# sensor_v2.net
KiCad netlist of a schematic drawn in EAGLE
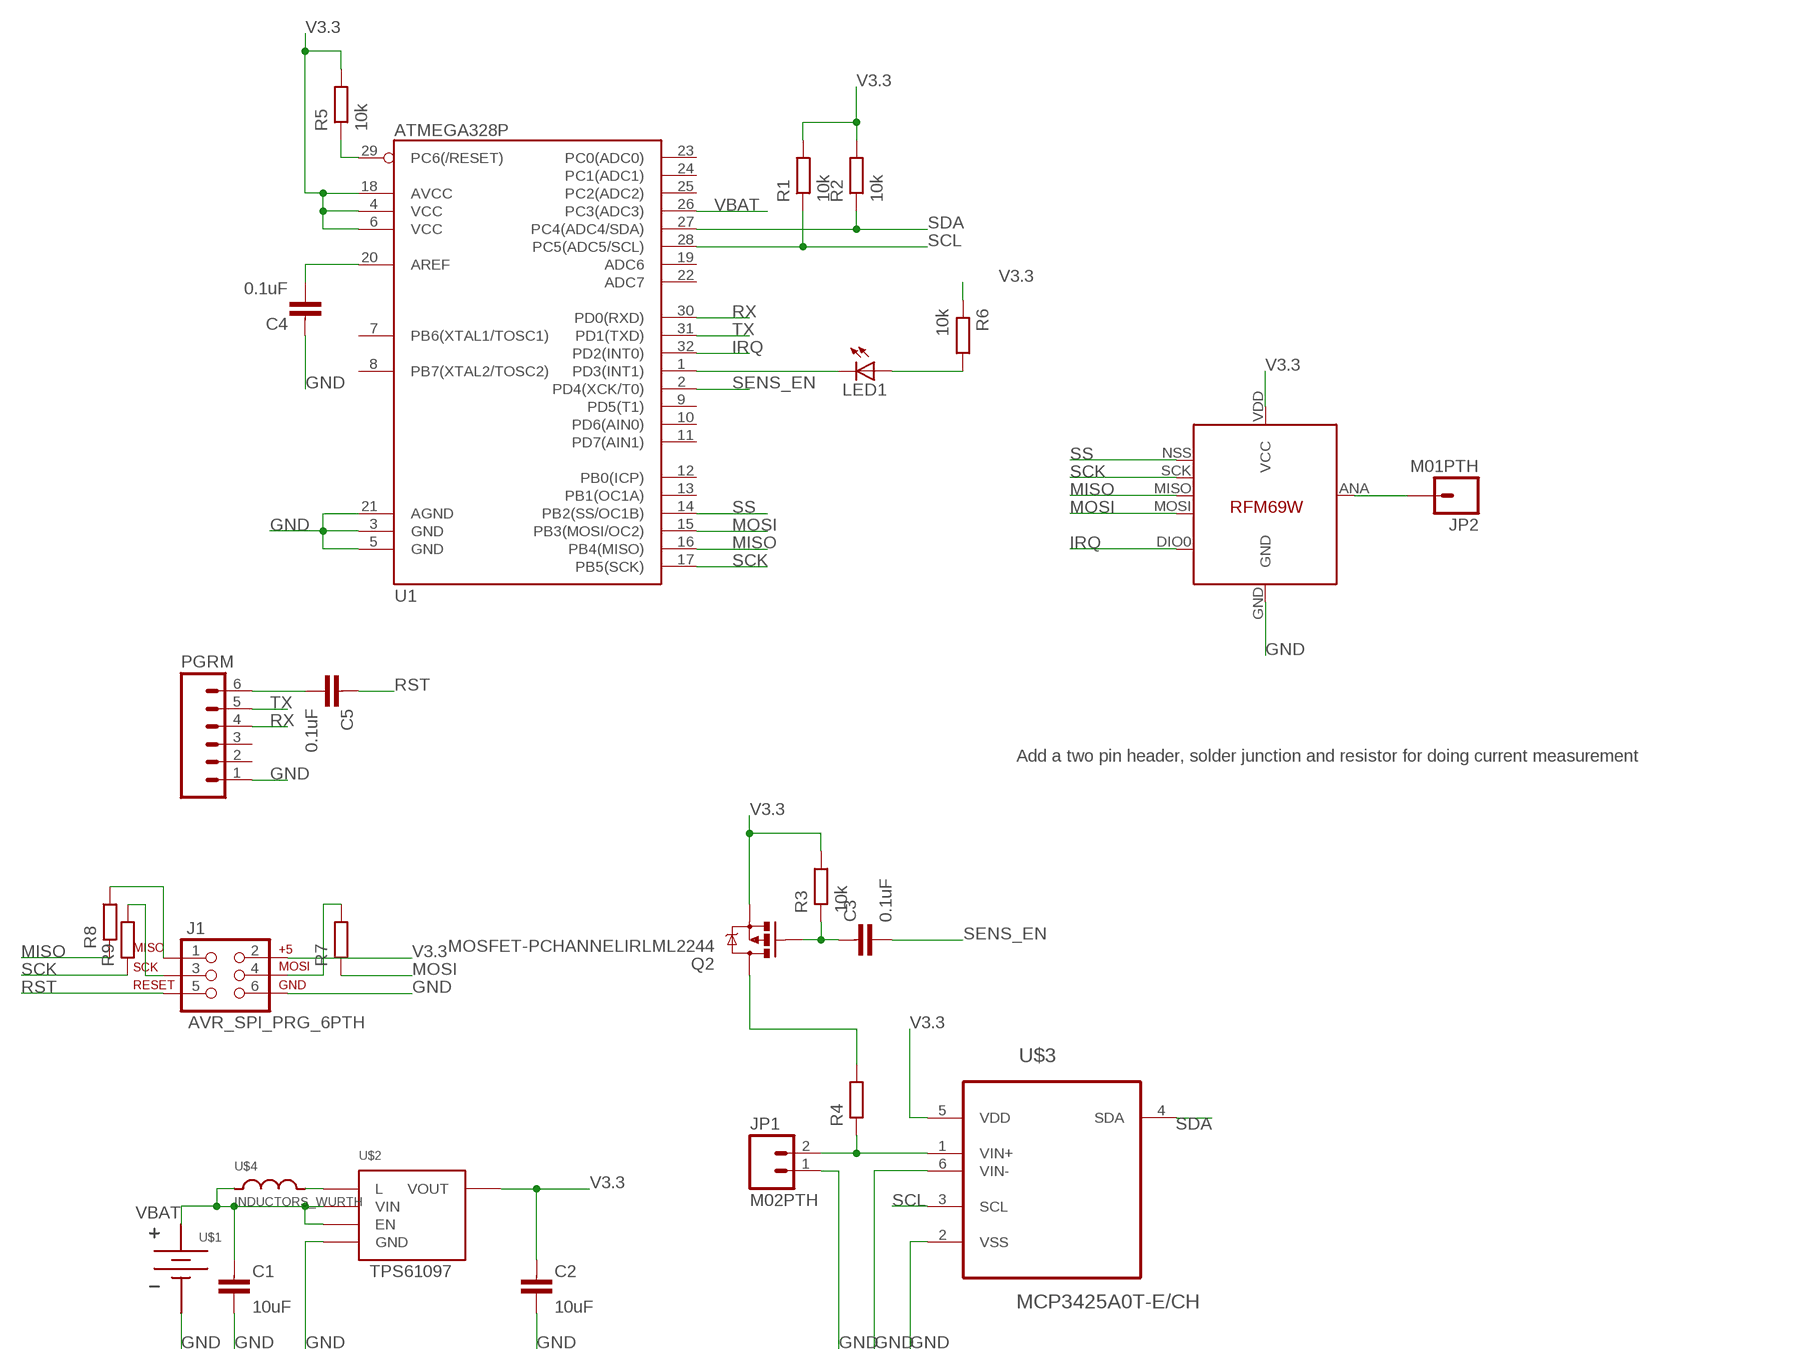
[diagram p0: schematic, sheet 1]

(export (version "E")
  (design (tool "Eeschema 10.0.6"))
  (components
    (comp (ref "C1")
      (value "10uF")
      (footprint "eagle-import:C0805-N")
      (libsource (lib "eagle-import") (part "CAPACITOR0805-N"))
    )
    (comp (ref "C2")
      (value "10uF")
      (footprint "eagle-import:C0805-N")
      (libsource (lib "eagle-import") (part "CAPACITOR0805-N"))
    )
    (comp (ref "C3")
      (value "0.1uF")
      (footprint "eagle-import:C0603-N")
      (libsource (lib "eagle-import") (part "CAPACITOR0603-N"))
    )
    (comp (ref "C4")
      (value "0.1uF")
      (footprint "eagle-import:C0603-N")
      (libsource (lib "eagle-import") (part "CAPACITOR0603-N"))
    )
    (comp (ref "C5")
      (value "0.1uF")
      (footprint "eagle-import:C0603-N")
      (libsource (lib "eagle-import") (part "CAPACITOR0603-N"))
    )
    (comp (ref "J1")
      (value "AVR_SPI_PRG_6PTH")
      (footprint "eagle-import:2X3")
      (libsource (lib "eagle-import") (part "AVR_SPI_PRG_6PTH"))
    )
    (comp (ref "JP1")
      (value "M02PTH")
      (footprint "eagle-import:1X02")
      (libsource (lib "eagle-import") (part "M02PTH"))
    )
    (comp (ref "JP2")
      (value "M01PTH")
      (footprint "eagle-import:1X01")
      (libsource (lib "eagle-import") (part "M01PTH"))
    )
    (comp (ref "LED1")
      (value "LED0603")
      (footprint "eagle-import:LED-0603")
      (libsource (lib "eagle-import") (part "LED0603"))
    )
    (comp (ref "PGRM")
      (value "M06LONGPADS")
      (footprint "eagle-import:1X06_LONGPADS")
      (libsource (lib "eagle-import") (part "M06LONGPADS"))
    )
    (comp (ref "Q2")
      (value "MOSFET-PCHANNELIRLML2244")
      (footprint "eagle-import:SOT23-3")
      (libsource (lib "eagle-import") (part "MOSFET-PCHANNELIRLML2244"))
    )
    (comp (ref "R1")
      (value "10k")
      (footprint "eagle-import:R0603-N")
      (libsource (lib "eagle-import") (part "RESISTOR0603-N"))
    )
    (comp (ref "R2")
      (value "10k")
      (footprint "eagle-import:R0603-N")
      (libsource (lib "eagle-import") (part "RESISTOR0603-N"))
    )
    (comp (ref "R3")
      (value "10k")
      (footprint "eagle-import:R0603-N")
      (libsource (lib "eagle-import") (part "RESISTOR0603-N"))
    )
    (comp (ref "R4")
      (value "RESISTOR0603-N")
      (footprint "eagle-import:R0603-N")
      (libsource (lib "eagle-import") (part "RESISTOR0603-N"))
    )
    (comp (ref "R5")
      (value "10k")
      (footprint "eagle-import:R0603-N")
      (libsource (lib "eagle-import") (part "RESISTOR0603-N"))
    )
    (comp (ref "R6")
      (value "10k")
      (footprint "eagle-import:R0603-N")
      (libsource (lib "eagle-import") (part "RESISTOR0603-N"))
    )
    (comp (ref "R7")
      (value "RESISTOR1206-N")
      (footprint "eagle-import:R1206-N")
      (libsource (lib "eagle-import") (part "RESISTOR1206-N"))
    )
    (comp (ref "R8")
      (value "RESISTOR1206-N")
      (footprint "eagle-import:R1206-N")
      (libsource (lib "eagle-import") (part "RESISTOR1206-N"))
    )
    (comp (ref "R9")
      (value "RESISTOR1206-N")
      (footprint "eagle-import:R1206-N")
      (libsource (lib "eagle-import") (part "RESISTOR1206-N"))
    )
    (comp (ref "U$1")
      (value "KEYSTONEAAHOLDER_2CELL")
      (footprint "eagle-import:KEYSTONEAAHOLDER_2CELL")
      (libsource (lib "eagle-import") (part "KEYSTONEAAHOLDER_2CELL"))
    )
    (comp (ref "U$2")
      (value "TPS61097-33")
      (footprint "eagle-import:SOT23-5")
      (libsource (lib "eagle-import") (part "TPS61097-33"))
    )
    (comp (ref "U$3")
      (value "MCP3425A0T-E/CH")
      (footprint "eagle-import:SOT95P270X145-6N")
      (libsource (lib "eagle-import") (part "MCP3425A0T-E/CH"))
    )
    (comp (ref "U$4")
      (value "INDUCTORS_WURTH")
      (footprint "eagle-import:WURTH_10UH_650MA")
      (libsource (lib "eagle-import") (part "INDUCTORS_WURTH"))
    )
    (comp (ref "U$5")
      (value "RFM69")
      (footprint "eagle-import:RFM69W-MINPADS")
      (libsource (lib "eagle-import") (part "RFM69"))
    )
    (comp (ref "U1")
      (value "ATMEGA328P")
      (footprint "eagle-import:TQFP32-08")
      (libsource (lib "eagle-import") (part "ATMEGA328_SMT"))
    )
  )
  (nets
    (net (code "1") (name "/GND") (class "Default")
      (node (ref "C1") (pin "2") (pinfunction "2_2") (pintype "passive"))
      (node (ref "C2") (pin "2") (pinfunction "2_2") (pintype "passive"))
      (node (ref "C4") (pin "1") (pinfunction "1_1") (pintype "passive"))
      (node (ref "J1") (pin "6") (pinfunction "6_6") (pintype "passive"))
      (node (ref "JP1") (pin "1") (pinfunction "1_1") (pintype "passive"))
      (node (ref "PGRM") (pin "1") (pinfunction "1_1") (pintype "passive"))
      (node (ref "U$1") (pin "P$2") (pinfunction "GND_P$2") (pintype "bidirectional"))
      (node (ref "U$2") (pin "P$2") (pinfunction "GND_P$2") (pintype "power_in"))
      (node (ref "U$3") (pin "2") (pinfunction "VSS_2") (pintype "passive"))
      (node (ref "U$3") (pin "6") (pinfunction "VIN-_6") (pintype "input"))
      (node (ref "U$5") (pin "GND") (pinfunction "GND_GND") (pintype "power_in"))
      (node (ref "U1") (pin "21") (pinfunction "AGND_21") (pintype "bidirectional"))
      (node (ref "U1") (pin "3") (pinfunction "GND_3") (pintype "bidirectional"))
      (node (ref "U1") (pin "5") (pinfunction "GND_5") (pintype "bidirectional"))
    )
    (net (code "2") (name "/IRQ") (class "Default")
      (node (ref "U$5") (pin "DIO0") (pinfunction "DIO0_DIO0") (pintype "open_collector"))
      (node (ref "U1") (pin "32") (pinfunction "PD2(INT0)_32") (pintype "bidirectional"))
    )
    (net (code "3") (name "/MISO") (class "Default")
      (node (ref "R8") (pin "1") (pinfunction "P$1_1") (pintype "passive"))
      (node (ref "U$5") (pin "MISO") (pinfunction "MISO_MISO") (pintype "input"))
      (node (ref "U1") (pin "16") (pinfunction "PB4(MISO)_16") (pintype "bidirectional"))
    )
    (net (code "4") (name "/MOSI") (class "Default")
      (node (ref "R7") (pin "1") (pinfunction "P$1_1") (pintype "passive"))
      (node (ref "U$5") (pin "MOSI") (pinfunction "MOSI_MOSI") (pintype "output"))
      (node (ref "U1") (pin "15") (pinfunction "PB3(MOSI/OC2)_15") (pintype "bidirectional"))
    )
    (net (code "5") (name "/RST") (class "Default")
      (node (ref "C5") (pin "1") (pinfunction "1_1") (pintype "passive"))
      (node (ref "J1") (pin "5") (pinfunction "5_5") (pintype "passive"))
      (node (ref "R5") (pin "1") (pinfunction "P$1_1") (pintype "passive"))
      (node (ref "U1") (pin "29") (pinfunction "PC6(/RESET)_29") (pintype "bidirectional"))
    )
    (net (code "6") (name "/RX") (class "Default")
      (node (ref "PGRM") (pin "4") (pinfunction "4_4") (pintype "passive"))
      (node (ref "U1") (pin "30") (pinfunction "PD0(RXD)_30") (pintype "bidirectional"))
    )
    (net (code "7") (name "/SCK") (class "Default")
      (node (ref "R9") (pin "1") (pinfunction "P$1_1") (pintype "passive"))
      (node (ref "U$5") (pin "SCK") (pinfunction "SCK_SCK") (pintype "input"))
      (node (ref "U1") (pin "17") (pinfunction "PB5(SCK)_17") (pintype "bidirectional"))
    )
    (net (code "8") (name "/SCL") (class "Default")
      (node (ref "R1") (pin "1") (pinfunction "P$1_1") (pintype "passive"))
      (node (ref "U$3") (pin "3") (pinfunction "SCL_3") (pintype "input"))
      (node (ref "U1") (pin "28") (pinfunction "PC5(ADC5/SCL)_28") (pintype "bidirectional"))
    )
    (net (code "9") (name "/SDA") (class "Default")
      (node (ref "R2") (pin "1") (pinfunction "P$1_1") (pintype "passive"))
      (node (ref "U$3") (pin "4") (pinfunction "SDA_4") (pintype "bidirectional"))
      (node (ref "U1") (pin "27") (pinfunction "PC4(ADC4/SDA)_27") (pintype "bidirectional"))
    )
    (net (code "10") (name "/SENS_EN") (class "Default")
      (node (ref "C3") (pin "2") (pinfunction "2_2") (pintype "passive"))
      (node (ref "U1") (pin "2") (pinfunction "PD4(XCK/T0)_2") (pintype "bidirectional"))
    )
    (net (code "11") (name "/SS") (class "Default")
      (node (ref "U$5") (pin "NSS") (pinfunction "SEL_NSS") (pintype "input"))
      (node (ref "U1") (pin "14") (pinfunction "PB2(SS/OC1B)_14") (pintype "bidirectional"))
    )
    (net (code "12") (name "/TX") (class "Default")
      (node (ref "PGRM") (pin "5") (pinfunction "5_5") (pintype "passive"))
      (node (ref "U1") (pin "31") (pinfunction "PD1(TXD)_31") (pintype "bidirectional"))
    )
    (net (code "13") (name "/V3.3") (class "Default")
      (node (ref "C2") (pin "1") (pinfunction "1_1") (pintype "passive"))
      (node (ref "J1") (pin "2") (pinfunction "2_2") (pintype "passive"))
      (node (ref "Q2") (pin "2") (pinfunction "S_2") (pintype "passive"))
      (node (ref "R1") (pin "2") (pinfunction "P$2_2") (pintype "passive"))
      (node (ref "R2") (pin "2") (pinfunction "P$2_2") (pintype "passive"))
      (node (ref "R3") (pin "2") (pinfunction "P$2_2") (pintype "passive"))
      (node (ref "R5") (pin "2") (pinfunction "P$2_2") (pintype "passive"))
      (node (ref "R6") (pin "1") (pinfunction "P$1_1") (pintype "passive"))
      (node (ref "U$2") (pin "P$4") (pinfunction "VOUT_P$4") (pintype "power_in"))
      (node (ref "U$3") (pin "5") (pinfunction "VDD_5") (pintype "power_in"))
      (node (ref "U$5") (pin "VDD") (pinfunction "VCC_VDD") (pintype "power_in"))
      (node (ref "U1") (pin "18") (pinfunction "AVCC_18") (pintype "bidirectional"))
      (node (ref "U1") (pin "4") (pinfunction "VCC_4") (pintype "bidirectional"))
      (node (ref "U1") (pin "6") (pinfunction "VCC_6") (pintype "bidirectional"))
    )
    (net (code "14") (name "/VBAT") (class "Default")
      (node (ref "C1") (pin "1") (pinfunction "1_1") (pintype "passive"))
      (node (ref "U$1") (pin "P$1") (pinfunction "VBAT_P$1") (pintype "bidirectional"))
      (node (ref "U$2") (pin "P$1") (pinfunction "VIN_P$1") (pintype "power_in"))
      (node (ref "U$2") (pin "P$3") (pinfunction "EN_P$3") (pintype "bidirectional"))
      (node (ref "U$4") (pin "P$2") (pinfunction "P$2_P$2") (pintype "passive"))
      (node (ref "U1") (pin "26") (pinfunction "PC3(ADC3)_26") (pintype "bidirectional"))
    )
    (net (code "15") (name "Net-(C5-Pad2)") (class "Default")
      (node (ref "C5") (pin "2") (pinfunction "2_2") (pintype "passive"))
      (node (ref "PGRM") (pin "6") (pinfunction "6_6") (pintype "passive"))
    )
    (net (code "16") (name "Net-(Q2-D)") (class "Default")
      (node (ref "Q2") (pin "3") (pinfunction "D_3") (pintype "passive"))
      (node (ref "R4") (pin "2") (pinfunction "P$2_2") (pintype "passive"))
    )
    (net (code "17") (name "Net-(Q2-G)") (class "Default")
      (node (ref "C3") (pin "1") (pinfunction "1_1") (pintype "passive"))
      (node (ref "Q2") (pin "1") (pinfunction "G_1") (pintype "passive"))
      (node (ref "R3") (pin "1") (pinfunction "P$1_1") (pintype "passive"))
    )
    (net (code "18") (name "Net-(R4-P$1)") (class "Default")
      (node (ref "JP1") (pin "2") (pinfunction "2_2") (pintype "passive"))
      (node (ref "R4") (pin "1") (pinfunction "P$1_1") (pintype "passive"))
      (node (ref "U$3") (pin "1") (pinfunction "VIN+_1") (pintype "input"))
    )
    (net (code "19") (name "Net-(R6-P$2)") (class "Default")
      (node (ref "LED1") (pin "A") (pinfunction "A_A") (pintype "passive"))
      (node (ref "R6") (pin "2") (pinfunction "P$2_2") (pintype "passive"))
    )
    (net (code "20") (name "Net-(R7-P$2)") (class "Default")
      (node (ref "J1") (pin "4") (pinfunction "4_4") (pintype "passive"))
      (node (ref "R7") (pin "2") (pinfunction "P$2_2") (pintype "passive"))
    )
    (net (code "21") (name "Net-(R8-P$2)") (class "Default")
      (node (ref "J1") (pin "1") (pinfunction "1_1") (pintype "passive"))
      (node (ref "R8") (pin "2") (pinfunction "P$2_2") (pintype "passive"))
    )
    (net (code "22") (name "Net-(R9-P$2)") (class "Default")
      (node (ref "J1") (pin "3") (pinfunction "3_3") (pintype "passive"))
      (node (ref "R9") (pin "2") (pinfunction "P$2_2") (pintype "passive"))
    )
    (net (code "23") (name "Net-(U$2-L)") (class "Default")
      (node (ref "U$2") (pin "P$5") (pinfunction "L_P$5") (pintype "bidirectional"))
      (node (ref "U$4") (pin "P$1") (pinfunction "P$1_P$1") (pintype "passive"))
    )
    (net (code "24") (name "Net-(U$5-ANT)") (class "Default")
      (node (ref "JP2") (pin "1") (pinfunction "1_1") (pintype "passive"))
      (node (ref "U$5") (pin "ANA") (pinfunction "ANT_ANA") (pintype "passive"))
    )
    (net (code "25") (name "Net-(U1-AREF)") (class "Default")
      (node (ref "C4") (pin "2") (pinfunction "2_2") (pintype "passive"))
      (node (ref "U1") (pin "20") (pinfunction "AREF_20") (pintype "bidirectional"))
    )
    (net (code "26") (name "Net-(U1-PD3(INT1))") (class "Default")
      (node (ref "LED1") (pin "C") (pinfunction "C_C") (pintype "passive"))
      (node (ref "U1") (pin "1") (pinfunction "PD3(INT1)_1") (pintype "bidirectional"))
    )
    (net (code "27") (name "unconnected-(PGRM-Pad2)") (class "Default")
      (node (ref "PGRM") (pin "2") (pinfunction "2_2") (pintype "passive"))
    )
    (net (code "28") (name "unconnected-(PGRM-Pad3)") (class "Default")
      (node (ref "PGRM") (pin "3") (pinfunction "3_3") (pintype "passive"))
    )
    (net (code "29") (name "unconnected-(U1-ADC6-Pad19)") (class "Default")
      (node (ref "U1") (pin "19") (pinfunction "ADC6_19") (pintype "bidirectional"))
    )
    (net (code "30") (name "unconnected-(U1-ADC7-Pad22)") (class "Default")
      (node (ref "U1") (pin "22") (pinfunction "ADC7_22") (pintype "bidirectional"))
    )
    (net (code "31") (name "unconnected-(U1-PB0(ICP)-Pad12)") (class "Default")
      (node (ref "U1") (pin "12") (pinfunction "PB0(ICP)_12") (pintype "bidirectional"))
    )
    (net (code "32") (name "unconnected-(U1-PB1(OC1A)-Pad13)") (class "Default")
      (node (ref "U1") (pin "13") (pinfunction "PB1(OC1A)_13") (pintype "bidirectional"))
    )
    (net (code "33") (name "unconnected-(U1-PB6(XTAL1{slash}TOSC1)-Pad7)") (class "Default")
      (node (ref "U1") (pin "7") (pinfunction "PB6(XTAL1/TOSC1)_7") (pintype "bidirectional"))
    )
    (net (code "34") (name "unconnected-(U1-PB7(XTAL2{slash}TOSC2)-Pad8)") (class "Default")
      (node (ref "U1") (pin "8") (pinfunction "PB7(XTAL2/TOSC2)_8") (pintype "bidirectional"))
    )
    (net (code "35") (name "unconnected-(U1-PC0(ADC0)-Pad23)") (class "Default")
      (node (ref "U1") (pin "23") (pinfunction "PC0(ADC0)_23") (pintype "bidirectional"))
    )
    (net (code "36") (name "unconnected-(U1-PC1(ADC1)-Pad24)") (class "Default")
      (node (ref "U1") (pin "24") (pinfunction "PC1(ADC1)_24") (pintype "bidirectional"))
    )
    (net (code "37") (name "unconnected-(U1-PC2(ADC2)-Pad25)") (class "Default")
      (node (ref "U1") (pin "25") (pinfunction "PC2(ADC2)_25") (pintype "bidirectional"))
    )
    (net (code "38") (name "unconnected-(U1-PD5(T1)-Pad9)") (class "Default")
      (node (ref "U1") (pin "9") (pinfunction "PD5(T1)_9") (pintype "bidirectional"))
    )
    (net (code "39") (name "unconnected-(U1-PD6(AIN0)-Pad10)") (class "Default")
      (node (ref "U1") (pin "10") (pinfunction "PD6(AIN0)_10") (pintype "bidirectional"))
    )
    (net (code "40") (name "unconnected-(U1-PD7(AIN1)-Pad11)") (class "Default")
      (node (ref "U1") (pin "11") (pinfunction "PD7(AIN1)_11") (pintype "bidirectional"))
    )
  )
)
